# RFM12B_Breakout.net
KiCad netlist of a schematic drawn in EAGLE
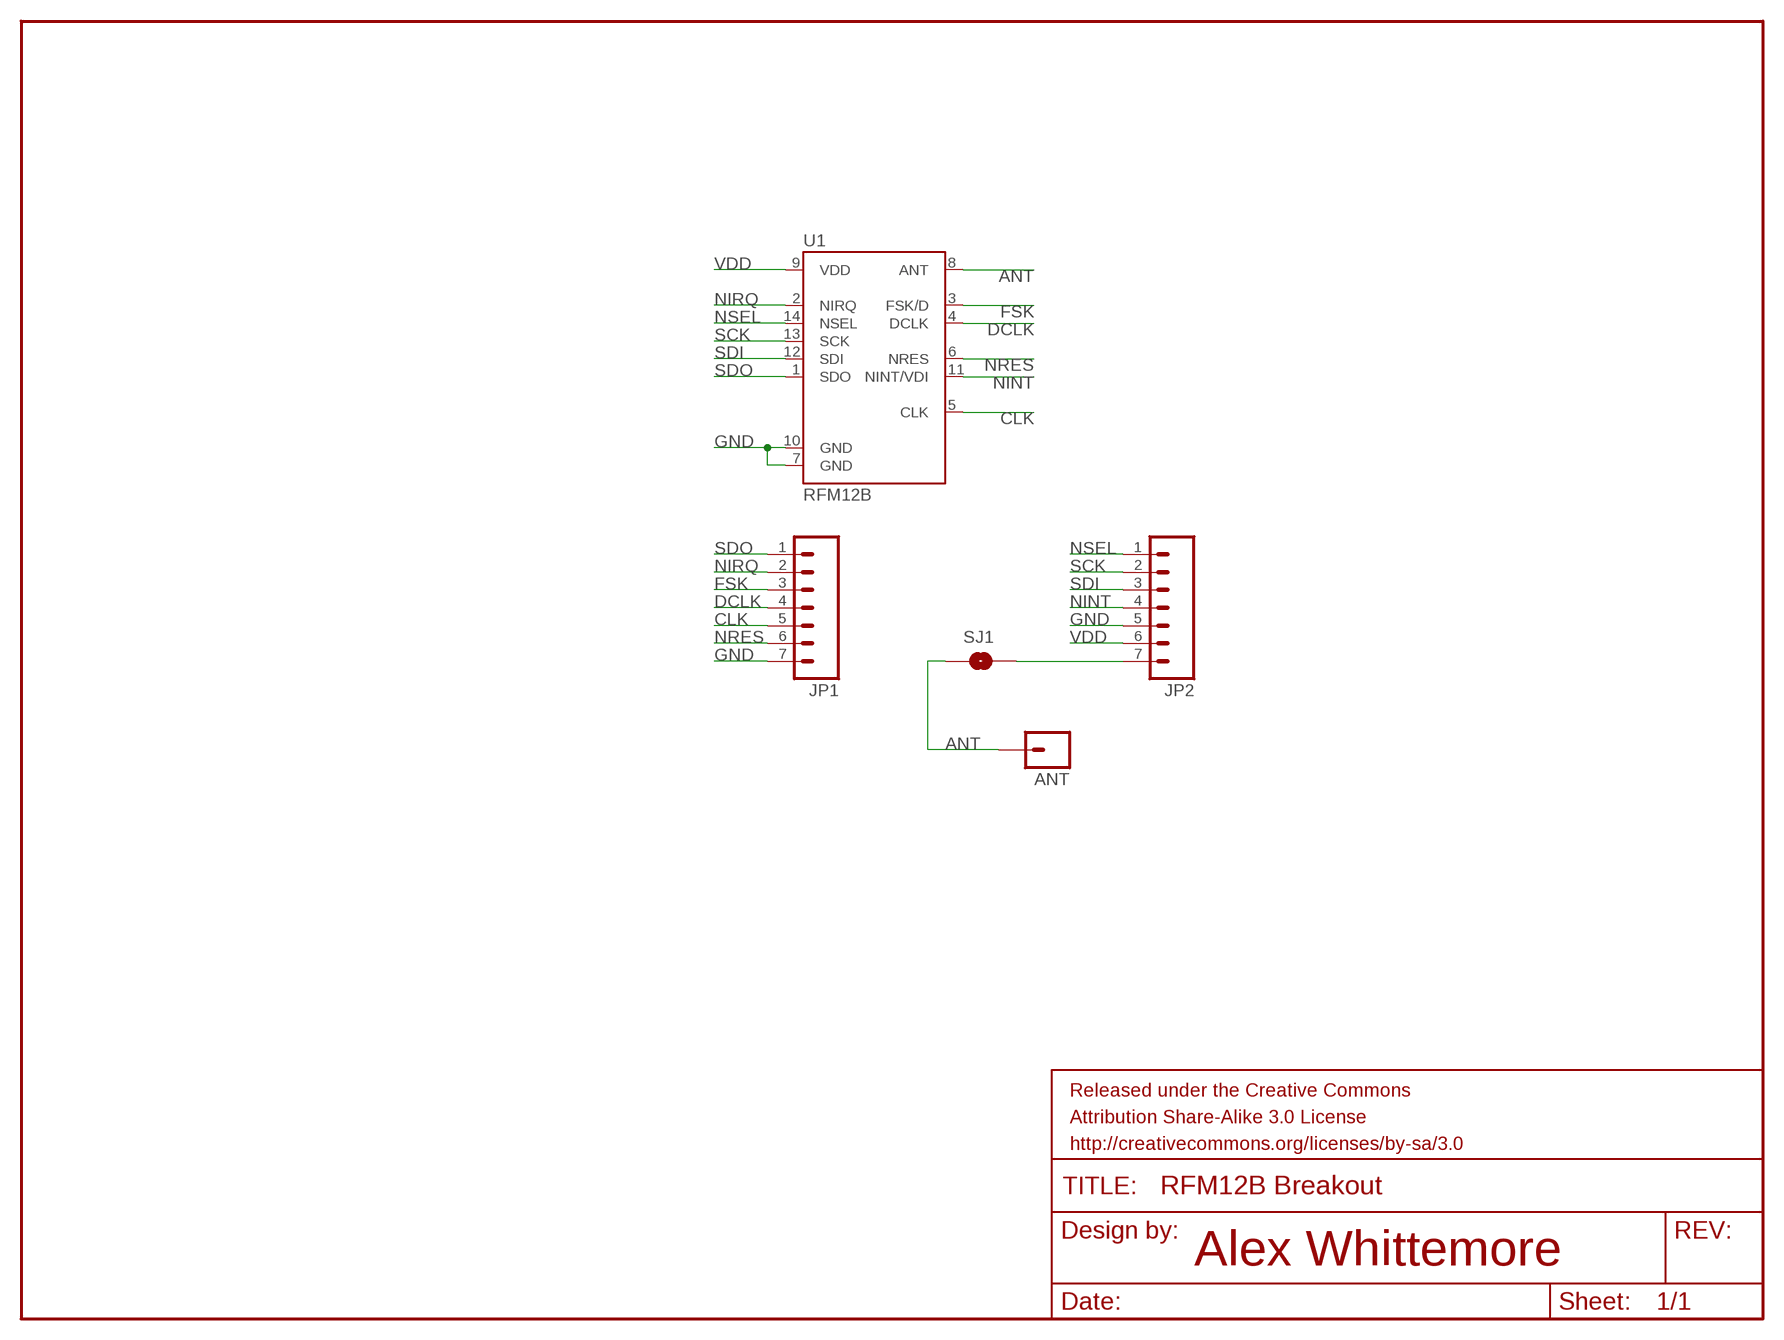
[diagram p0: schematic, sheet 1]

(export (version "E")
  (design (tool "Eeschema 10.0.6"))
  (components
    (comp (ref "ANT")
      (value "M01PTH")
      (footprint "eagle-import:1X01")
      (libsource (lib "eagle-import") (part "M01PTH"))
    )
    (comp (ref "JP1")
      (value "M07LOCK")
      (footprint "eagle-import:1X07_LOCK")
      (libsource (lib "eagle-import") (part "M07LOCK"))
    )
    (comp (ref "JP2")
      (value "M07LOCK")
      (footprint "eagle-import:1X07_LOCK")
      (libsource (lib "eagle-import") (part "M07LOCK"))
    )
    (comp (ref "SJ1")
      (value "SOLDERJUMPERNO")
      (footprint "eagle-import:SJ_2S-NO")
      (libsource (lib "eagle-import") (part "SOLDERJUMPERNO"))
    )
    (comp (ref "U1")
      (value "RFM12B")
      (footprint "eagle-import:RFM12-XXX-S2")
      (libsource (lib "eagle-import") (part "RFM12B"))
    )
  )
  (nets
    (net (code "1") (name "/ANT") (class "Default")
      (node (ref "ANT") (pin "1") (pinfunction "1_1") (pintype "passive"))
      (node (ref "SJ1") (pin "1") (pinfunction "1_1") (pintype "passive"))
      (node (ref "U1") (pin "8") (pinfunction "ANT_8") (pintype "bidirectional"))
    )
    (net (code "2") (name "/CLK") (class "Default")
      (node (ref "JP1") (pin "5") (pinfunction "5_5") (pintype "passive"))
      (node (ref "U1") (pin "5") (pinfunction "CLK_5") (pintype "output"))
    )
    (net (code "3") (name "/DCLK") (class "Default")
      (node (ref "JP1") (pin "4") (pinfunction "4_4") (pintype "passive"))
      (node (ref "U1") (pin "4") (pinfunction "DCLK_4") (pintype "bidirectional"))
    )
    (net (code "4") (name "/FSK") (class "Default")
      (node (ref "JP1") (pin "3") (pinfunction "3_3") (pintype "passive"))
      (node (ref "U1") (pin "3") (pinfunction "FSK/D_3") (pintype "bidirectional"))
    )
    (net (code "5") (name "/GND") (class "Default")
      (node (ref "JP1") (pin "7") (pinfunction "7_7") (pintype "passive"))
      (node (ref "JP2") (pin "5") (pinfunction "5_5") (pintype "passive"))
      (node (ref "U1") (pin "10") (pinfunction "GND_10") (pintype "power_in"))
      (node (ref "U1") (pin "7") (pinfunction "GND_7") (pintype "power_in"))
    )
    (net (code "6") (name "/NINT") (class "Default")
      (node (ref "JP2") (pin "4") (pinfunction "4_4") (pintype "passive"))
      (node (ref "U1") (pin "11") (pinfunction "NINT/VDI_11") (pintype "bidirectional"))
    )
    (net (code "7") (name "/NIRQ") (class "Default")
      (node (ref "JP1") (pin "2") (pinfunction "2_2") (pintype "passive"))
      (node (ref "U1") (pin "2") (pinfunction "NIRQ_2") (pintype "output"))
    )
    (net (code "8") (name "/NRES") (class "Default")
      (node (ref "JP1") (pin "6") (pinfunction "6_6") (pintype "passive"))
      (node (ref "U1") (pin "6") (pinfunction "NRES_6") (pintype "bidirectional"))
    )
    (net (code "9") (name "/NSEL") (class "Default")
      (node (ref "JP2") (pin "1") (pinfunction "1_1") (pintype "passive"))
      (node (ref "U1") (pin "14") (pinfunction "NSEL_14") (pintype "input"))
    )
    (net (code "10") (name "/SCK") (class "Default")
      (node (ref "JP2") (pin "2") (pinfunction "2_2") (pintype "passive"))
      (node (ref "U1") (pin "13") (pinfunction "SCK_13") (pintype "input"))
    )
    (net (code "11") (name "/SDI") (class "Default")
      (node (ref "JP2") (pin "3") (pinfunction "3_3") (pintype "passive"))
      (node (ref "U1") (pin "12") (pinfunction "SDI_12") (pintype "input"))
    )
    (net (code "12") (name "/SDO") (class "Default")
      (node (ref "JP1") (pin "1") (pinfunction "1_1") (pintype "passive"))
      (node (ref "U1") (pin "1") (pinfunction "SDO_1") (pintype "output"))
    )
    (net (code "13") (name "/VDD") (class "Default")
      (node (ref "JP2") (pin "6") (pinfunction "6_6") (pintype "passive"))
      (node (ref "U1") (pin "9") (pinfunction "VDD_9") (pintype "bidirectional"))
    )
    (net (code "14") (name "Net-(JP2-Pad7)") (class "Default")
      (node (ref "JP2") (pin "7") (pinfunction "7_7") (pintype "passive"))
      (node (ref "SJ1") (pin "2") (pinfunction "2_2") (pintype "passive"))
    )
  )
)
